# Main_Backup2.net
KiCad netlist of a schematic drawn in EAGLE
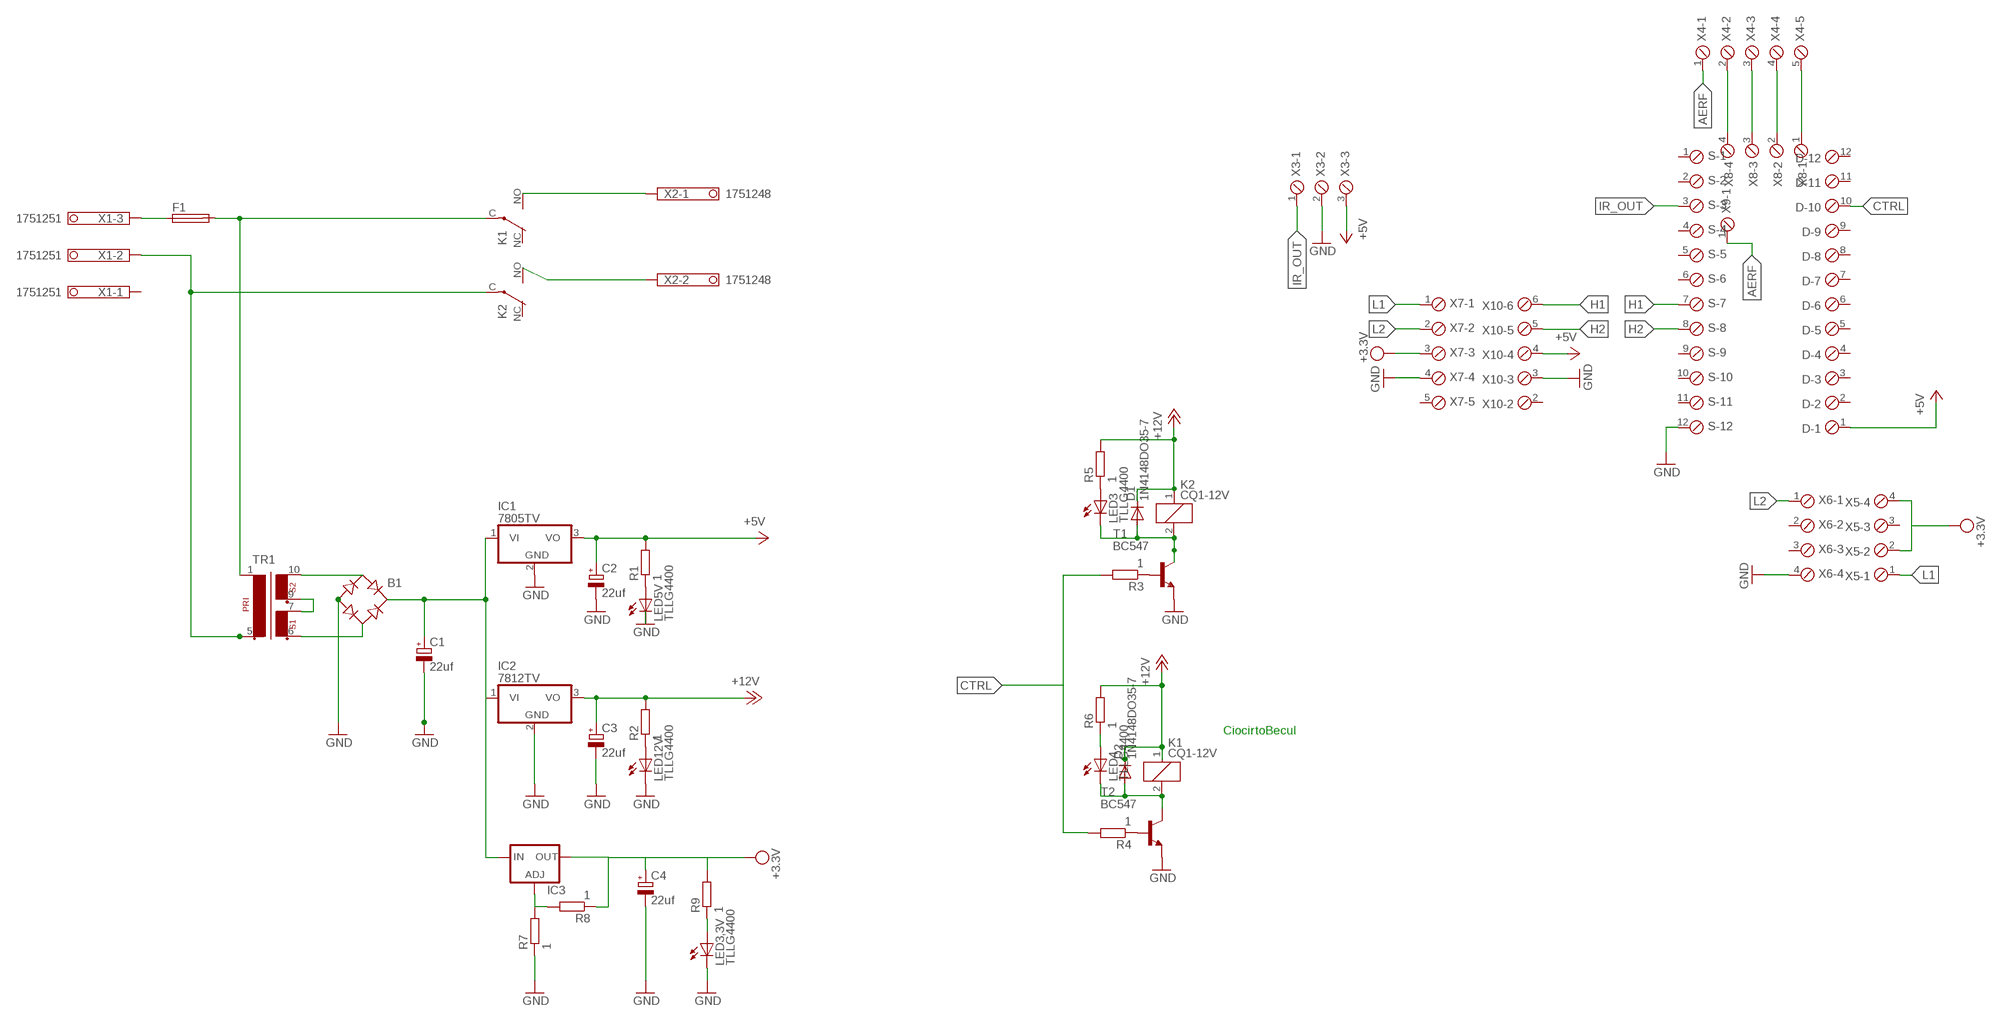
[diagram p0: schematic, sheet 1]

(export (version "E")
  (design (tool "Eeschema 10.0.6"))
  (components
    (comp (ref "B1")
      (value "RB1A")
      (footprint "eagle-import:RB1A")
      (libsource (lib "eagle-import") (part "RB1A"))
    )
    (comp (ref "C1")
      (value "22uf")
      (footprint "eagle-import:E2-4")
      (libsource (lib "eagle-import") (part "CPOL-EUE2-4"))
    )
    (comp (ref "C2")
      (value "22uf")
      (footprint "eagle-import:E2-4")
      (libsource (lib "eagle-import") (part "CPOL-EUE2-4"))
    )
    (comp (ref "C3")
      (value "22uf")
      (footprint "eagle-import:E2-4")
      (libsource (lib "eagle-import") (part "CPOL-EUE2-4"))
    )
    (comp (ref "C4")
      (value "22uf")
      (footprint "eagle-import:E2-4")
      (libsource (lib "eagle-import") (part "CPOL-EUE2-4"))
    )
    (comp (ref "D")
      (value "MPT12")
      (footprint "eagle-import:12POL254")
      (libsource (lib "eagle-import") (part "MPT12"))
    )
    (comp (ref "D1")
      (value "1N4148DO35-7")
      (footprint "eagle-import:DO35-7")
      (libsource (lib "eagle-import") (part "1N4148DO35-7"))
    )
    (comp (ref "D2")
      (value "1N4148DO35-7")
      (footprint "eagle-import:DO35-7")
      (libsource (lib "eagle-import") (part "1N4148DO35-7"))
    )
    (comp (ref "F1")
      (value "SH25")
      (footprint "eagle-import:SH25")
      (fields (field (name "MF") "SCHURTER") (field (name "MPN") "0031.8211"))
      (libsource (lib "eagle-import") (part "SH25"))
    )
    (comp (ref "IC1")
      (value "7805TV")
      (footprint "eagle-import:TO220V")
      (libsource (lib "eagle-import") (part "78TV05"))
    )
    (comp (ref "IC2")
      (value "7812TV")
      (footprint "eagle-import:TO220V")
      (libsource (lib "eagle-import") (part "78TV12"))
    )
    (comp (ref "IC3")
      (value "LM317TS")
      (footprint "eagle-import:317TS")
      (libsource (lib "eagle-import") (part "LM317TS"))
    )
    (comp (ref "K1")
      (value "CQ1-12V")
      (footprint "eagle-import:CQ1")
      (libsource (lib "eagle-import") (part "CQ1-12V"))
    )
    (comp (ref "K2")
      (value "CQ1-12V")
      (footprint "eagle-import:CQ1")
      (libsource (lib "eagle-import") (part "CQ1-12V"))
    )
    (comp (ref "LED3")
      (value "TLLG4400")
      (footprint "eagle-import:LED3MM")
      (fields (field (name "MF") "VISHAY SEMICONDUCTOR"))
      (libsource (lib "eagle-import") (part "TLLG4400"))
    )
    (comp (ref "LED3,3V")
      (value "TLLG4400")
      (footprint "eagle-import:LED3MM")
      (fields (field (name "MF") "VISHAY SEMICONDUCTOR"))
      (libsource (lib "eagle-import") (part "TLLG4400"))
    )
    (comp (ref "LED4")
      (value "TLLG4400")
      (footprint "eagle-import:LED3MM")
      (fields (field (name "MF") "VISHAY SEMICONDUCTOR"))
      (libsource (lib "eagle-import") (part "TLLG4400"))
    )
    (comp (ref "LED5V")
      (value "TLLG4400")
      (footprint "eagle-import:LED3MM")
      (fields (field (name "MF") "VISHAY SEMICONDUCTOR"))
      (libsource (lib "eagle-import") (part "TLLG4400"))
    )
    (comp (ref "LED12V")
      (value "TLLG4400")
      (footprint "eagle-import:LED3MM")
      (fields (field (name "MF") "VISHAY SEMICONDUCTOR"))
      (libsource (lib "eagle-import") (part "TLLG4400"))
    )
    (comp (ref "R1")
      (value "1")
      (footprint "eagle-import:0204_5")
      (libsource (lib "eagle-import") (part "R-EU_0204/5"))
    )
    (comp (ref "R2")
      (value "1")
      (footprint "eagle-import:0204_5")
      (libsource (lib "eagle-import") (part "R-EU_0204/5"))
    )
    (comp (ref "R3")
      (value "1")
      (footprint "eagle-import:0204_5")
      (libsource (lib "eagle-import") (part "R-EU_0204/5"))
    )
    (comp (ref "R4")
      (value "1")
      (footprint "eagle-import:0204_5")
      (libsource (lib "eagle-import") (part "R-EU_0204/5"))
    )
    (comp (ref "R5")
      (value "1")
      (footprint "eagle-import:0204_5")
      (libsource (lib "eagle-import") (part "R-EU_0204/5"))
    )
    (comp (ref "R6")
      (value "1")
      (footprint "eagle-import:0204_5")
      (libsource (lib "eagle-import") (part "R-EU_0204/5"))
    )
    (comp (ref "R7")
      (value "1")
      (footprint "eagle-import:0204_5")
      (libsource (lib "eagle-import") (part "R-EU_0204/5"))
    )
    (comp (ref "R8")
      (value "1")
      (footprint "eagle-import:0204_5")
      (libsource (lib "eagle-import") (part "R-EU_0204/5"))
    )
    (comp (ref "R9")
      (value "1")
      (footprint "eagle-import:0204_5")
      (libsource (lib "eagle-import") (part "R-EU_0204/5"))
    )
    (comp (ref "S")
      (value "MPT12")
      (footprint "eagle-import:12POL254")
      (libsource (lib "eagle-import") (part "MPT12"))
    )
    (comp (ref "T1")
      (value "BC547")
      (footprint "eagle-import:TO92")
      (libsource (lib "eagle-import") (part "BC547"))
    )
    (comp (ref "T2")
      (value "BC547")
      (footprint "eagle-import:TO92")
      (libsource (lib "eagle-import") (part "BC547"))
    )
    (comp (ref "TR1")
      (value "EI30-2")
      (footprint "eagle-import:EI30-2")
      (libsource (lib "eagle-import") (part "EI30-2"))
    )
    (comp (ref "X1")
      (value "1751251")
      (footprint "eagle-import:1751251")
      (libsource (lib "eagle-import") (part "1751251"))
    )
    (comp (ref "X2")
      (value "1751248")
      (footprint "eagle-import:1751248")
      (libsource (lib "eagle-import") (part "1751248"))
    )
    (comp (ref "X3")
      (value "MPT3")
      (footprint "eagle-import:3POL254")
      (libsource (lib "eagle-import") (part "MPT3"))
    )
    (comp (ref "X4")
      (value "MPT5")
      (footprint "eagle-import:5POL254")
      (libsource (lib "eagle-import") (part "MPT5"))
    )
    (comp (ref "X5")
      (value "MPT4")
      (footprint "eagle-import:4POL254")
      (libsource (lib "eagle-import") (part "MPT4"))
    )
    (comp (ref "X6")
      (value "MPT4")
      (footprint "eagle-import:4POL254")
      (libsource (lib "eagle-import") (part "MPT4"))
    )
    (comp (ref "X7")
      (value "MPT6")
      (footprint "eagle-import:6POL254")
      (libsource (lib "eagle-import") (part "MPT6"))
    )
    (comp (ref "X8")
      (value "MPT4")
      (footprint "eagle-import:4POL254")
      (libsource (lib "eagle-import") (part "MPT4"))
    )
    (comp (ref "X9")
      (value "MPT2")
      (footprint "eagle-import:2POL254")
      (libsource (lib "eagle-import") (part "MPT2"))
    )
    (comp (ref "X10")
      (value "MPT6")
      (footprint "eagle-import:6POL254")
      (libsource (lib "eagle-import") (part "MPT6"))
    )
  )
  (nets
    (net (code "1") (name "+3.3V") (class "Default")
      (node (ref "C4") (pin "+") (pinfunction "+_+") (pintype "passive"))
      (node (ref "IC3") (pin "2") (pinfunction "OUT_2") (pintype "passive"))
      (node (ref "R8") (pin "1") (pinfunction "1_1") (pintype "passive"))
      (node (ref "R9") (pin "2") (pinfunction "2_2") (pintype "passive"))
      (node (ref "X5") (pin "2") (pinfunction "1_2") (pintype "passive"))
      (node (ref "X5") (pin "4") (pinfunction "1_4") (pintype "passive"))
      (node (ref "X7") (pin "3") (pinfunction "1_3") (pintype "passive"))
    )
    (net (code "2") (name "+5V") (class "Default")
      (node (ref "C2") (pin "+") (pinfunction "+_+") (pintype "passive"))
      (node (ref "D") (pin "1") (pinfunction "1_1") (pintype "passive"))
      (node (ref "IC1") (pin "3") (pinfunction "VO_3") (pintype "passive"))
      (node (ref "R1") (pin "2") (pinfunction "2_2") (pintype "passive"))
      (node (ref "X10") (pin "4") (pinfunction "1_4") (pintype "passive"))
      (node (ref "X3") (pin "3") (pinfunction "1_3") (pintype "passive"))
    )
    (net (code "3") (name "+12V") (class "Default")
      (node (ref "C3") (pin "+") (pinfunction "+_+") (pintype "passive"))
      (node (ref "D1") (pin "C") (pinfunction "C_C") (pintype "passive"))
      (node (ref "D2") (pin "C") (pinfunction "C_C") (pintype "passive"))
      (node (ref "IC2") (pin "3") (pinfunction "VO_3") (pintype "passive"))
      (node (ref "K1") (pin "1") (pinfunction "1_1") (pintype "passive"))
      (node (ref "K2") (pin "1") (pinfunction "1_1") (pintype "passive"))
      (node (ref "R2") (pin "2") (pinfunction "2_2") (pintype "passive"))
      (node (ref "R5") (pin "2") (pinfunction "2_2") (pintype "passive"))
      (node (ref "R6") (pin "2") (pinfunction "2_2") (pintype "passive"))
    )
    (net (code "4") (name "AERF") (class "Default")
      (node (ref "X4") (pin "1") (pinfunction "1_1") (pintype "passive"))
      (node (ref "X9") (pin "1") (pinfunction "1_1") (pintype "passive"))
    )
    (net (code "5") (name "CTRL") (class "Default")
      (node (ref "D") (pin "10") (pinfunction "1_10") (pintype "passive"))
      (node (ref "R3") (pin "2") (pinfunction "2_2") (pintype "passive"))
      (node (ref "R4") (pin "2") (pinfunction "2_2") (pintype "passive"))
    )
    (net (code "6") (name "GND") (class "Default")
      (node (ref "B1") (pin "-") (pinfunction "-_-") (pintype "passive"))
      (node (ref "C1") (pin "-") (pinfunction "-_-") (pintype "passive"))
      (node (ref "C2") (pin "-") (pinfunction "-_-") (pintype "passive"))
      (node (ref "C3") (pin "-") (pinfunction "-_-") (pintype "passive"))
      (node (ref "C4") (pin "-") (pinfunction "-_-") (pintype "passive"))
      (node (ref "IC1") (pin "2") (pinfunction "GND_2") (pintype "passive"))
      (node (ref "IC2") (pin "2") (pinfunction "GND_2") (pintype "passive"))
      (node (ref "LED12V") (pin "K") (pinfunction "C_K") (pintype "passive"))
      (node (ref "LED3,3V") (pin "K") (pinfunction "C_K") (pintype "passive"))
      (node (ref "LED5V") (pin "K") (pinfunction "C_K") (pintype "passive"))
      (node (ref "R7") (pin "1") (pinfunction "1_1") (pintype "passive"))
      (node (ref "S") (pin "12") (pinfunction "1_12") (pintype "passive"))
      (node (ref "T1") (pin "1") (pinfunction "E_1") (pintype "passive"))
      (node (ref "T2") (pin "1") (pinfunction "E_1") (pintype "passive"))
      (node (ref "X10") (pin "3") (pinfunction "1_3") (pintype "passive"))
      (node (ref "X3") (pin "2") (pinfunction "1_2") (pintype "passive"))
      (node (ref "X6") (pin "4") (pinfunction "1_4") (pintype "passive"))
      (node (ref "X7") (pin "4") (pinfunction "1_4") (pintype "passive"))
    )
    (net (code "7") (name "H1") (class "Default")
      (node (ref "S") (pin "7") (pinfunction "1_7") (pintype "passive"))
      (node (ref "X10") (pin "6") (pinfunction "1_6") (pintype "passive"))
    )
    (net (code "8") (name "H2") (class "Default")
      (node (ref "S") (pin "8") (pinfunction "1_8") (pintype "passive"))
      (node (ref "X10") (pin "5") (pinfunction "1_5") (pintype "passive"))
    )
    (net (code "9") (name "IR_OUT") (class "Default")
      (node (ref "S") (pin "3") (pinfunction "1_3") (pintype "passive"))
      (node (ref "X3") (pin "1") (pinfunction "1_1") (pintype "passive"))
    )
    (net (code "10") (name "L1") (class "Default")
      (node (ref "X5") (pin "1") (pinfunction "1_1") (pintype "passive"))
      (node (ref "X7") (pin "1") (pinfunction "1_1") (pintype "passive"))
    )
    (net (code "11") (name "L2") (class "Default")
      (node (ref "X6") (pin "1") (pinfunction "1_1") (pintype "passive"))
      (node (ref "X7") (pin "2") (pinfunction "1_2") (pintype "passive"))
    )
    (net (code "12") (name "Net-(IC1-VI)") (class "Default")
      (node (ref "B1") (pin "+") (pinfunction "+_+") (pintype "passive"))
      (node (ref "C1") (pin "+") (pinfunction "+_+") (pintype "passive"))
      (node (ref "IC1") (pin "1") (pinfunction "VI_1") (pintype "input"))
      (node (ref "IC2") (pin "1") (pinfunction "VI_1") (pintype "input"))
      (node (ref "IC3") (pin "3") (pinfunction "IN_3") (pintype "input"))
    )
    (net (code "13") (name "Net-(IC3-ADJ)") (class "Default")
      (node (ref "IC3") (pin "1") (pinfunction "ADJ_1") (pintype "input"))
      (node (ref "R7") (pin "2") (pinfunction "2_2") (pintype "passive"))
      (node (ref "R8") (pin "2") (pinfunction "2_2") (pintype "passive"))
    )
    (net (code "14") (name "Net-(K1B-P)") (class "Default")
      (node (ref "F1") (pin "2") (pinfunction "2_2") (pintype "passive"))
      (node (ref "K1") (pin "C") (pinfunction "P_C") (pintype "passive"))
      (node (ref "TR1") (pin "1") (pinfunction "1_1") (pintype "passive"))
    )
    (net (code "15") (name "Net-(K1B-S)") (class "Default")
      (node (ref "K1") (pin "NO") (pinfunction "S_NO") (pintype "passive"))
      (node (ref "X2") (pin "1") (pinfunction "K_1") (pintype "passive"))
    )
    (net (code "16") (name "Net-(K2B-P)") (class "Default")
      (node (ref "K2") (pin "C") (pinfunction "P_C") (pintype "passive"))
      (node (ref "TR1") (pin "5") (pinfunction "2_5") (pintype "passive"))
      (node (ref "X1") (pin "2") (pinfunction "K_2") (pintype "passive"))
    )
    (net (code "17") (name "Net-(K2B-S)") (class "Default")
      (node (ref "K2") (pin "NO") (pinfunction "S_NO") (pintype "passive"))
      (node (ref "X2") (pin "2") (pinfunction "K_2") (pintype "passive"))
    )
    (net (code "18") (name "Net-(LED3,3V-PadA)") (class "Default")
      (node (ref "LED3,3V") (pin "A") (pinfunction "A_A") (pintype "passive"))
      (node (ref "R9") (pin "1") (pinfunction "1_1") (pintype "passive"))
    )
    (net (code "19") (name "Net-(LED3-C)") (class "Default")
      (node (ref "D1") (pin "A") (pinfunction "A_A") (pintype "passive"))
      (node (ref "K2") (pin "2") (pinfunction "2_2") (pintype "passive"))
      (node (ref "LED3") (pin "K") (pinfunction "C_K") (pintype "passive"))
      (node (ref "T1") (pin "3") (pinfunction "C_3") (pintype "passive"))
    )
    (net (code "20") (name "Net-(LED3-PadA)") (class "Default")
      (node (ref "LED3") (pin "A") (pinfunction "A_A") (pintype "passive"))
      (node (ref "R5") (pin "1") (pinfunction "1_1") (pintype "passive"))
    )
    (net (code "21") (name "Net-(LED4-C)") (class "Default")
      (node (ref "D2") (pin "A") (pinfunction "A_A") (pintype "passive"))
      (node (ref "K1") (pin "2") (pinfunction "2_2") (pintype "passive"))
      (node (ref "LED4") (pin "K") (pinfunction "C_K") (pintype "passive"))
      (node (ref "T2") (pin "3") (pinfunction "C_3") (pintype "passive"))
    )
    (net (code "22") (name "Net-(LED4-PadA)") (class "Default")
      (node (ref "LED4") (pin "A") (pinfunction "A_A") (pintype "passive"))
      (node (ref "R6") (pin "1") (pinfunction "1_1") (pintype "passive"))
    )
    (net (code "23") (name "Net-(LED5V-PadA)") (class "Default")
      (node (ref "LED5V") (pin "A") (pinfunction "A_A") (pintype "passive"))
      (node (ref "R1") (pin "1") (pinfunction "1_1") (pintype "passive"))
    )
    (net (code "24") (name "Net-(LED12V-PadA)") (class "Default")
      (node (ref "LED12V") (pin "A") (pinfunction "A_A") (pintype "passive"))
      (node (ref "R2") (pin "1") (pinfunction "1_1") (pintype "passive"))
    )
    (net (code "25") (name "Net-(T1-B)") (class "Default")
      (node (ref "R3") (pin "1") (pinfunction "1_1") (pintype "passive"))
      (node (ref "T1") (pin "2") (pinfunction "B_2") (pintype "passive"))
    )
    (net (code "26") (name "Net-(T2-B)") (class "Default")
      (node (ref "R4") (pin "1") (pinfunction "1_1") (pintype "passive"))
      (node (ref "T2") (pin "2") (pinfunction "B_2") (pintype "passive"))
    )
    (net (code "27") (name "Net-(TR1-3)") (class "Default")
      (node (ref "B1") (pin "AC2") (pinfunction "AC2_AC2") (pintype "passive"))
      (node (ref "TR1") (pin "6") (pinfunction "3_6") (pintype "passive"))
    )
    (net (code "28") (name "Net-(TR1-4)") (class "Default")
      (node (ref "TR1") (pin "7") (pinfunction "4_7") (pintype "passive"))
      (node (ref "TR1") (pin "9") (pinfunction "5_9") (pintype "passive"))
    )
    (net (code "29") (name "Net-(TR1-6)") (class "Default")
      (node (ref "B1") (pin "AC1") (pinfunction "AC1_AC1") (pintype "passive"))
      (node (ref "TR1") (pin "10") (pinfunction "6_10") (pintype "passive"))
    )
    (net (code "30") (name "Net-(X1C-K)") (class "Default")
      (node (ref "F1") (pin "1") (pinfunction "1_1") (pintype "passive"))
      (node (ref "X1") (pin "3") (pinfunction "K_3") (pintype "passive"))
    )
    (net (code "31") (name "Net-(X4B-1)") (class "Default")
      (node (ref "X4") (pin "2") (pinfunction "1_2") (pintype "passive"))
      (node (ref "X8") (pin "4") (pinfunction "1_4") (pintype "passive"))
    )
    (net (code "32") (name "Net-(X4C-1)") (class "Default")
      (node (ref "X4") (pin "3") (pinfunction "1_3") (pintype "passive"))
      (node (ref "X8") (pin "3") (pinfunction "1_3") (pintype "passive"))
    )
    (net (code "33") (name "Net-(X4D-1)") (class "Default")
      (node (ref "X4") (pin "4") (pinfunction "1_4") (pintype "passive"))
      (node (ref "X8") (pin "2") (pinfunction "1_2") (pintype "passive"))
    )
    (net (code "34") (name "Net-(X4E-1)") (class "Default")
      (node (ref "X4") (pin "5") (pinfunction "1_5") (pintype "passive"))
      (node (ref "X8") (pin "1") (pinfunction "1_1") (pintype "passive"))
    )
    (net (code "35") (name "unconnected-(DC-1-Pad11)") (class "Default")
      (node (ref "D") (pin "11") (pinfunction "1_11") (pintype "passive"))
    )
    (net (code "36") (name "unconnected-(DD-1-Pad12)") (class "Default")
      (node (ref "D") (pin "12") (pinfunction "1_12") (pintype "passive"))
    )
    (net (code "37") (name "unconnected-(DE-1-Pad2)") (class "Default")
      (node (ref "D") (pin "2") (pinfunction "1_2") (pintype "passive"))
    )
    (net (code "38") (name "unconnected-(DF-1-Pad3)") (class "Default")
      (node (ref "D") (pin "3") (pinfunction "1_3") (pintype "passive"))
    )
    (net (code "39") (name "unconnected-(DG-1-Pad4)") (class "Default")
      (node (ref "D") (pin "4") (pinfunction "1_4") (pintype "passive"))
    )
    (net (code "40") (name "unconnected-(DH-1-Pad5)") (class "Default")
      (node (ref "D") (pin "5") (pinfunction "1_5") (pintype "passive"))
    )
    (net (code "41") (name "unconnected-(DI-1-Pad6)") (class "Default")
      (node (ref "D") (pin "6") (pinfunction "1_6") (pintype "passive"))
    )
    (net (code "42") (name "unconnected-(DJ-1-Pad7)") (class "Default")
      (node (ref "D") (pin "7") (pinfunction "1_7") (pintype "passive"))
    )
    (net (code "43") (name "unconnected-(DK-1-Pad8)") (class "Default")
      (node (ref "D") (pin "8") (pinfunction "1_8") (pintype "passive"))
    )
    (net (code "44") (name "unconnected-(DL-1-Pad9)") (class "Default")
      (node (ref "D") (pin "9") (pinfunction "1_9") (pintype "passive"))
    )
    (net (code "45") (name "unconnected-(K1B-O-PadNC)") (class "Default")
      (node (ref "K1") (pin "NC") (pinfunction "O_NC") (pintype "passive"))
    )
    (net (code "46") (name "unconnected-(K2B-O-PadNC)") (class "Default")
      (node (ref "K2") (pin "NC") (pinfunction "O_NC") (pintype "passive"))
    )
    (net (code "47") (name "unconnected-(S-Pad1)") (class "Default")
      (node (ref "S") (pin "1") (pinfunction "1_1") (pintype "passive"))
    )
    (net (code "48") (name "unconnected-(SB-1-Pad10)") (class "Default")
      (node (ref "S") (pin "10") (pinfunction "1_10") (pintype "passive"))
    )
    (net (code "49") (name "unconnected-(SC-1-Pad11)") (class "Default")
      (node (ref "S") (pin "11") (pinfunction "1_11") (pintype "passive"))
    )
    (net (code "50") (name "unconnected-(SE-1-Pad2)") (class "Default")
      (node (ref "S") (pin "2") (pinfunction "1_2") (pintype "passive"))
    )
    (net (code "51") (name "unconnected-(SG-1-Pad4)") (class "Default")
      (node (ref "S") (pin "4") (pinfunction "1_4") (pintype "passive"))
    )
    (net (code "52") (name "unconnected-(SH-1-Pad5)") (class "Default")
      (node (ref "S") (pin "5") (pinfunction "1_5") (pintype "passive"))
    )
    (net (code "53") (name "unconnected-(SI-1-Pad6)") (class "Default")
      (node (ref "S") (pin "6") (pinfunction "1_6") (pintype "passive"))
    )
    (net (code "54") (name "unconnected-(SL-1-Pad9)") (class "Default")
      (node (ref "S") (pin "9") (pinfunction "1_9") (pintype "passive"))
    )
    (net (code "55") (name "unconnected-(X1A-K-Pad1)") (class "Default")
      (node (ref "X1") (pin "1") (pinfunction "K_1") (pintype "passive"))
    )
    (net (code "56") (name "unconnected-(X5C-1-Pad3)") (class "Default")
      (node (ref "X5") (pin "3") (pinfunction "1_3") (pintype "passive"))
    )
    (net (code "57") (name "unconnected-(X6B-1-Pad2)") (class "Default")
      (node (ref "X6") (pin "2") (pinfunction "1_2") (pintype "passive"))
    )
    (net (code "58") (name "unconnected-(X6C-1-Pad3)") (class "Default")
      (node (ref "X6") (pin "3") (pinfunction "1_3") (pintype "passive"))
    )
    (net (code "59") (name "unconnected-(X7E-1-Pad5)") (class "Default")
      (node (ref "X7") (pin "5") (pinfunction "1_5") (pintype "passive"))
    )
    (net (code "60") (name "unconnected-(X10B-1-Pad2)") (class "Default")
      (node (ref "X10") (pin "2") (pinfunction "1_2") (pintype "passive"))
    )
  )
)
